# Top_DMX8x8A-v1.net
KiCad netlist of a schematic drawn in Altium Designer
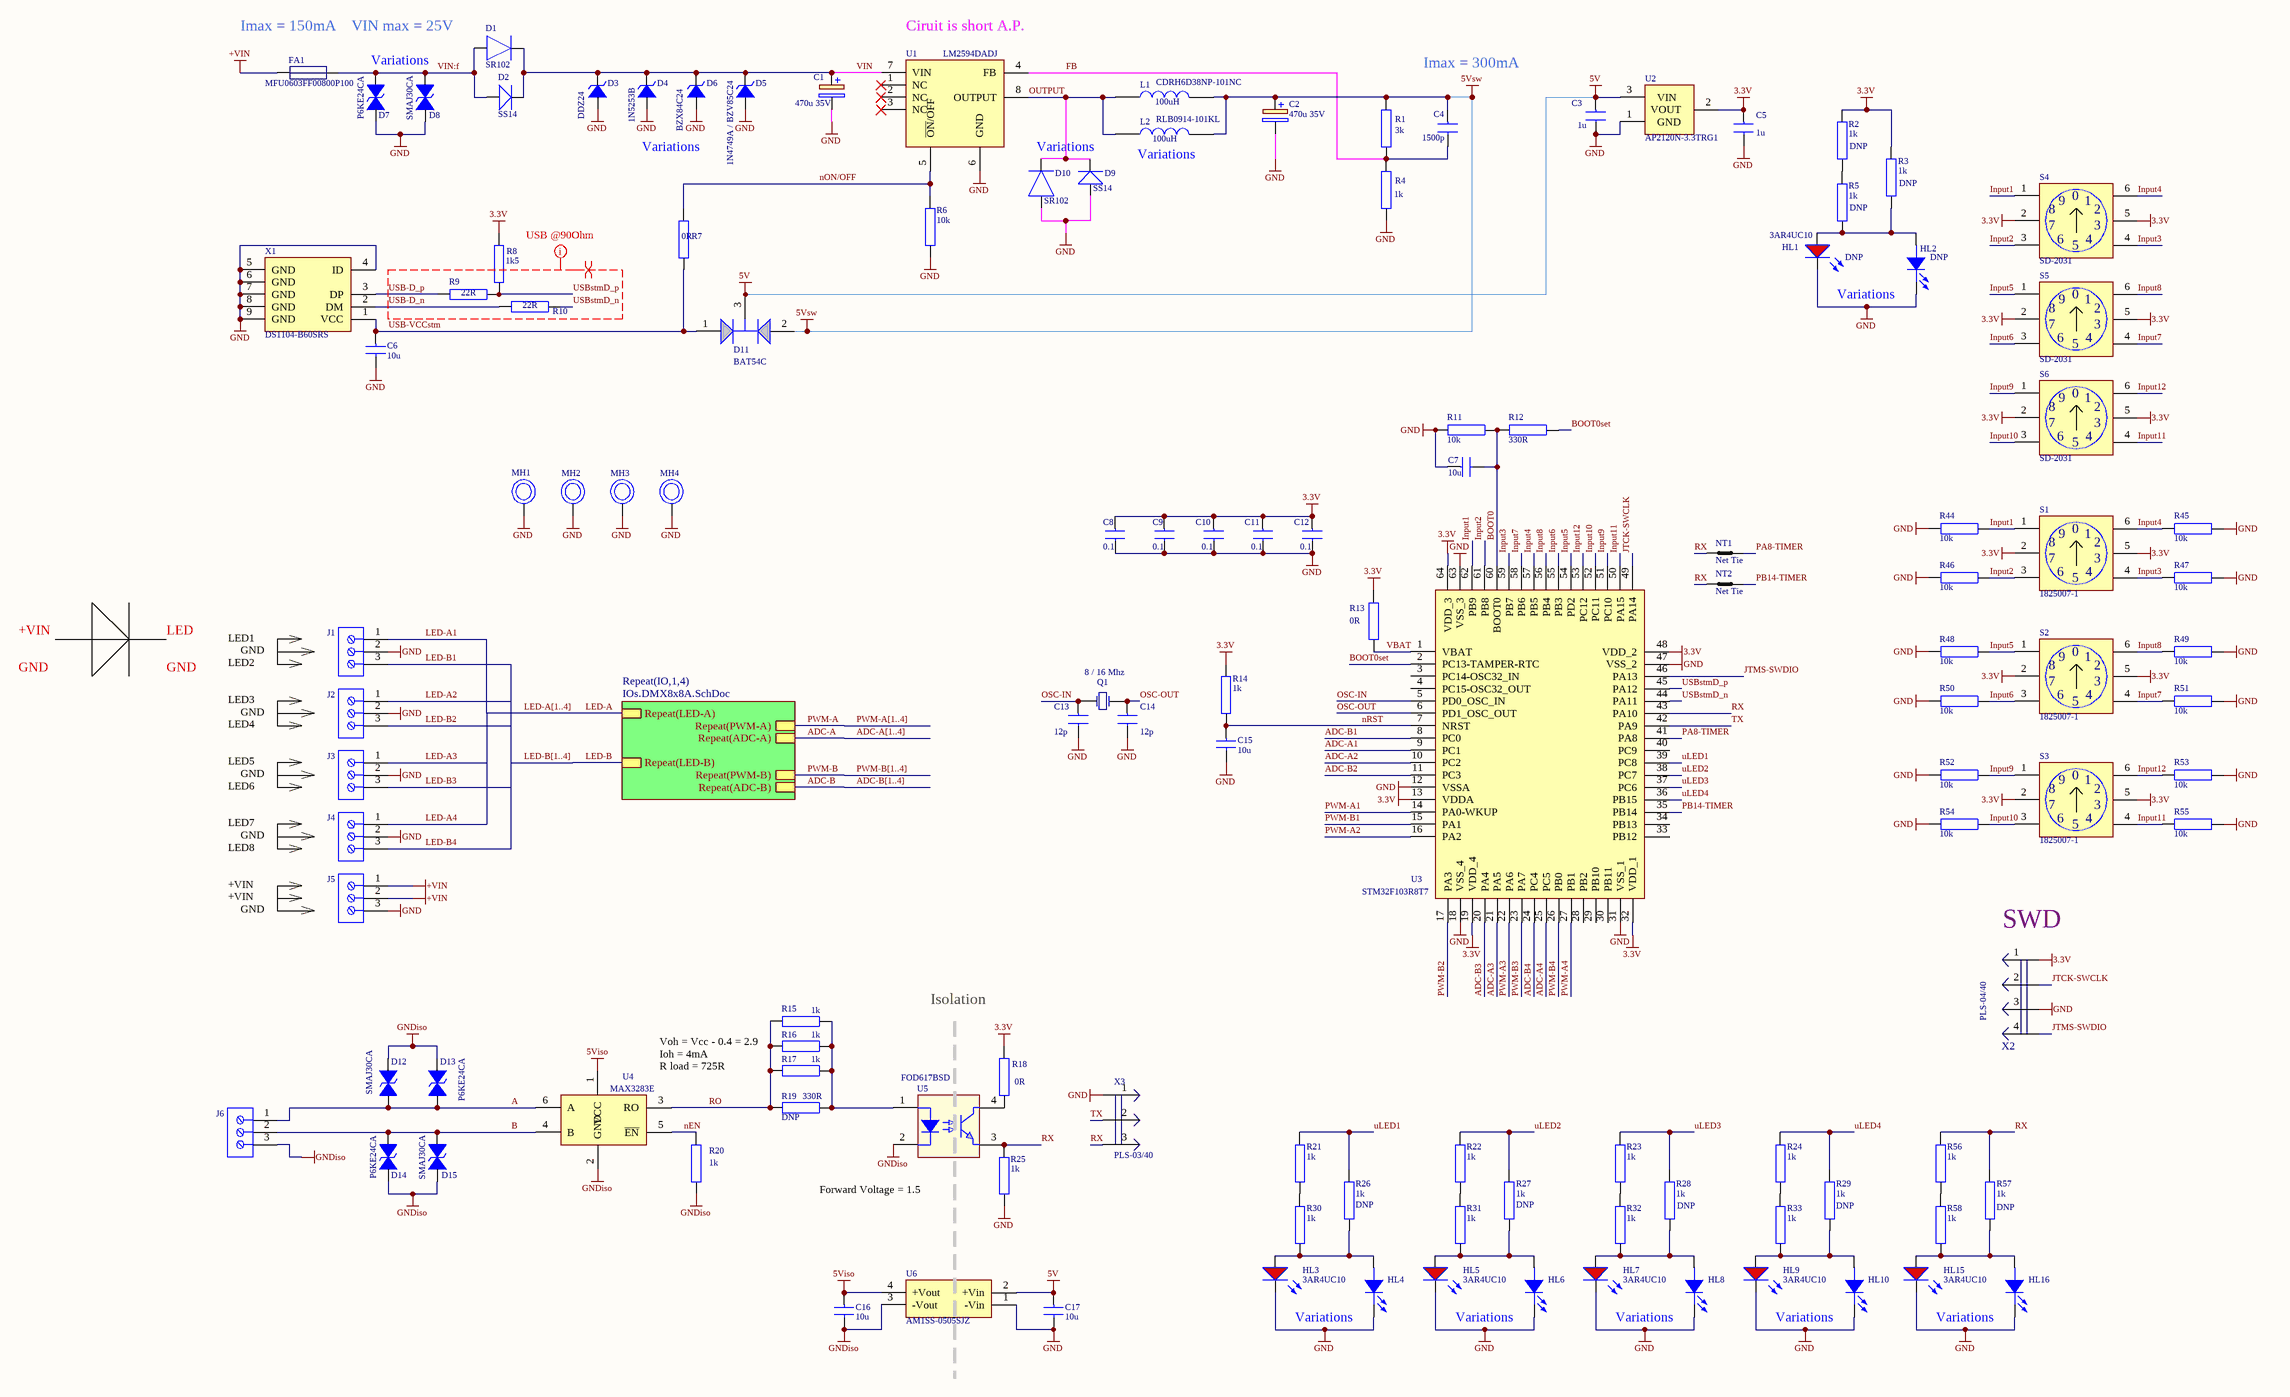
[diagram p0: Top.DMX8x8A-v1.SchDoc]

(export (version "E")
  (design (tool "Eeschema 10.0.6"))
  (components
    (comp (ref "C1")
      (value "470u 35V")
      (footprint "CAPPRD500W60D1025H1750")
      (description "Radial Lead Aluminum Electrolytic Capacitors")
      (fields (field (name "Comment") "35ZL470MEFC10X20"))
      (libsource (lib "DMX512") (part "35ZL470MEFC10X20"))
    )
    (comp (ref "C2")
      (value "470u 35V")
      (footprint "CAPPRD500W60D1025H1750")
      (description "Radial Lead Aluminum Electrolytic Capacitors")
      (fields (field (name "Comment") "35ZL470MEFC10X20"))
      (libsource (lib "DMX512") (part "35ZL470MEFC10X20"))
    )
    (comp (ref "C3")
      (value "1u")
      (footprint "Chip C 0402 - 1206")
      (description "Ceramic Chip Capacitor")
      (fields (field (name "Comment") "1u 50V 5%"))
      (libsource (lib "Capacitors") (part "Ceramic SMD Cap_R"))
    )
    (comp (ref "C4")
      (value "1500p")
      (footprint "Chip C 0402 - 1206")
      (description "Ceramic Chip Capacitor")
      (fields (field (name "Comment") "1500p 25V 20%"))
      (libsource (lib "Capacitors") (part "Ceramic SMD Cap_R"))
    )
    (comp (ref "C5")
      (value "1u")
      (footprint "Chip C 0402 - 1206")
      (description "Ceramic Chip Capacitor")
      (fields (field (name "Comment") "1u 50V 5%"))
      (libsource (lib "Capacitors") (part "Ceramic SMD Cap_R"))
    )
    (comp (ref "C6")
      (value "10u")
      (footprint "Chip C 0402 - 1206")
      (description "Ceramic Chip Capacitor")
      (fields (field (name "Comment") "10u 50V 5%"))
      (libsource (lib "Capacitors") (part "Ceramic SMD Cap_R"))
    )
    (comp (ref "C7")
      (value "10u")
      (footprint "Chip C 0402 - 1206")
      (description "Ceramic Chip Capacitor")
      (fields (field (name "Comment") "10u 50V 5%"))
      (libsource (lib "Capacitors") (part "Ceramic SMD Cap_R"))
    )
    (comp (ref "C8")
      (value "0.1")
      (footprint "Chip C 0402 - 1206")
      (description "Ceramic Chip Capacitor")
      (fields (field (name "Comment") "0.1 25V 20%"))
      (libsource (lib "Capacitors") (part "Ceramic SMD Cap_R"))
    )
    (comp (ref "C9")
      (value "0.1")
      (footprint "Chip C 0402 - 1206")
      (description "Ceramic Chip Capacitor")
      (fields (field (name "Comment") "0.1 25V 20%"))
      (libsource (lib "Capacitors") (part "Ceramic SMD Cap_R"))
    )
    (comp (ref "C10")
      (value "0.1")
      (footprint "Chip C 0402 - 1206")
      (description "Ceramic Chip Capacitor")
      (fields (field (name "Comment") "0.1 25V 20%"))
      (libsource (lib "Capacitors") (part "Ceramic SMD Cap_R"))
    )
    (comp (ref "C11")
      (value "0.1")
      (footprint "Chip C 0402 - 1206")
      (description "Ceramic Chip Capacitor")
      (fields (field (name "Comment") "0.1 25V 20%"))
      (libsource (lib "Capacitors") (part "Ceramic SMD Cap_R"))
    )
    (comp (ref "C12")
      (value "0.1")
      (footprint "Chip C 0402 - 1206")
      (description "Ceramic Chip Capacitor")
      (fields (field (name "Comment") "0.1 25V 20%"))
      (libsource (lib "Capacitors") (part "Ceramic SMD Cap_R"))
    )
    (comp (ref "C13")
      (value "12p")
      (footprint "Chip C 0402 - 1206")
      (description "Ceramic Chip Capacitor")
      (fields (field (name "Comment") "12p 25V 20%"))
      (libsource (lib "Capacitors") (part "Ceramic SMD Cap_R"))
    )
    (comp (ref "C14")
      (value "12p")
      (footprint "Chip C 0402 - 1206")
      (description "Ceramic Chip Capacitor")
      (fields (field (name "Comment") "12p 25V 20%"))
      (libsource (lib "Capacitors") (part "Ceramic SMD Cap_R"))
    )
    (comp (ref "C15")
      (value "10u")
      (footprint "Chip C 0402 - 1206")
      (description "Ceramic Chip Capacitor")
      (fields (field (name "Comment") "10u 50V 5%"))
      (libsource (lib "Capacitors") (part "Ceramic SMD Cap_R"))
    )
    (comp (ref "C16")
      (value "10u")
      (footprint "Chip C 0402 - 1206")
      (description "Ceramic Chip Capacitor")
      (fields (field (name "Comment") "10u 50V 5%"))
      (libsource (lib "Capacitors") (part "Ceramic SMD Cap_R"))
    )
    (comp (ref "C17")
      (value "10u")
      (footprint "Chip C 0402 - 1206")
      (description "Ceramic Chip Capacitor")
      (fields (field (name "Comment") "10u 50V 5%"))
      (libsource (lib "Capacitors") (part "Ceramic SMD Cap_R"))
    )
    (comp (ref "D1")
      (value "SR102")
      (footprint "DO-204AL (DO-41)")
      (description "Schottky Barrier Rectifier")
      (libsource (lib "DMX512") (part "SR102"))
    )
    (comp (ref "D2")
      (value "SS14")
      (footprint "DO-214AC (SMA)")
      (description "Surface Mount Schottky Barrier Rectifier 1A")
      (libsource (lib "DMX512") (part "SS14"))
    )
    (comp (ref "D3")
      (value "DDZ24")
      (footprint "SOD323F")
      (description "Zener 0.5w SOD323F")
      (fields (field (name "MFR") "Diodes Incorporated"))
      (libsource (lib "Diodes") (part "DDZ"))
    )
    (comp (ref "D4")
      (value "1N5253B")
      (footprint "DO-204AH (DO-35).SLDPRT")
      (description "Zener DO-35")
      (fields (field (name "MFR") "ON Semi"))
      (libsource (lib "DMX512") (part "1N5253B"))
    )
    (comp (ref "D5")
      (value "1N4749A / BZV85C24")
      (footprint "DO-204AL (DO-41)")
      (description "Zener DO-41")
      (libsource (lib "DMX512") (part "Zener DO-41"))
    )
    (comp (ref "D6")
      (value "BZX84C24")
      (footprint "SOT-23-3 (3)")
      (description "Zener regulator, 27V")
      (fields (field (name "MFR") "ON Semi"))
      (libsource (lib "Diodes") (part "BZX84C13LT1G"))
    )
    (comp (ref "D7")
      (value "P6KE24CA")
      (footprint "DIOAD1910W90L670D310 (DO-15)")
      (description "TVS Axial 600W Unipolar 24V")
      (libsource (lib "DMX512") (part "P6KE"))
    )
    (comp (ref "D8")
      (value "SMAJ30CA")
      (footprint "DO-214AC (SMA) biplar")
      (description "TVS Uni 30V")
      (fields (field (name "MFR") "ST"))
      (libsource (lib "TVS") (part "SMAJ30CA"))
    )
    (comp (ref "D9")
      (value "SS14")
      (footprint "DO-214AC (SMA)")
      (description "Surface Mount Schottky Barrier Rectifier 1A")
      (libsource (lib "DMX512") (part "SS12"))
    )
    (comp (ref "D10")
      (value "SR102")
      (footprint "DO-204AL (DO-41)")
      (description "Schottky Barrier Rectifier")
      (libsource (lib "DMX512") (part "SR102"))
    )
    (comp (ref "D11")
      (value "BAT54C")
      (footprint "SOT-23-3 (3)")
      (description "SURFACE MOUNT SCHOTTKY BARRIER DIODE")
      (libsource (lib "Diodes") (part "BAT54C"))
    )
    (comp (ref "D12")
      (value "SMAJ30CA")
      (footprint "DO-214AC (SMA) biplar")
      (description "TVS Uni 30V")
      (fields (field (name "MFR") "ST"))
      (libsource (lib "TVS") (part "SMAJ30CA"))
    )
    (comp (ref "D13")
      (value "P6KE24CA")
      (footprint "DIOAD1910W90L670D310 (DO-15)")
      (description "TVS Axial 600W Unipolar 24V")
      (libsource (lib "DMX512") (part "P6KE"))
    )
    (comp (ref "D14")
      (value "P6KE24CA")
      (footprint "DIOAD1910W90L670D310 (DO-15)")
      (description "TVS Axial 600W Unipolar 24V")
      (libsource (lib "DMX512") (part "P6KE"))
    )
    (comp (ref "D15")
      (value "SMAJ30CA")
      (footprint "DO-214AC (SMA) biplar")
      (description "TVS Uni 30V")
      (fields (field (name "MFR") "ST"))
      (libsource (lib "TVS") (part "SMAJ30CA"))
    )
    (comp (ref "FA1")
      (value "MFU0603FF00800P100")
      (footprint "FUSC1608X55N")
      (description "Thin Film Chip Fuse")
      (libsource (lib "DMX512") (part "Fuse MFU"))
    )
    (comp (ref "HL1")
      (value "3AR4UC10")
      (footprint "LED-2pin 2.54mm")
      (description "LED 3mm Red")
      (fields (field (name "DNP") "DNP"))
      (libsource (lib "DMX512") (part "3AR4UC10"))
    )
    (comp (ref "HL2")
      (value "? Any")
      (footprint "LED SMD 0805")
      (description "LED 0805")
      (fields (field (name "DNP") "DNP"))
      (libsource (lib "DMX512") (part "LED 0805"))
    )
    (comp (ref "HL3")
      (value "3AR4UC10")
      (footprint "LED-2pin 2.54mm")
      (description "LED 3mm Red")
      (libsource (lib "DMX512") (part "3AR4UC10"))
    )
    (comp (ref "HL4")
      (value "? Any")
      (footprint "LED SMD 0805")
      (description "LED 0805")
      (libsource (lib "DMX512") (part "LED 0805"))
    )
    (comp (ref "HL5")
      (value "3AR4UC10")
      (footprint "LED-2pin 2.54mm")
      (description "LED 3mm Red")
      (libsource (lib "DMX512") (part "3AR4UC10"))
    )
    (comp (ref "HL6")
      (value "? Any")
      (footprint "LED SMD 0805")
      (description "LED 0805")
      (libsource (lib "DMX512") (part "LED 0805"))
    )
    (comp (ref "HL7")
      (value "3AR4UC10")
      (footprint "LED-2pin 2.54mm")
      (description "LED 3mm Red")
      (libsource (lib "DMX512") (part "3AR4UC10"))
    )
    (comp (ref "HL8")
      (value "? Any")
      (footprint "LED SMD 0805")
      (description "LED 0805")
      (libsource (lib "DMX512") (part "LED 0805"))
    )
    (comp (ref "HL9")
      (value "3AR4UC10")
      (footprint "LED-2pin 2.54mm")
      (description "LED 3mm Red")
      (libsource (lib "DMX512") (part "3AR4UC10"))
    )
    (comp (ref "HL10")
      (value "? Any")
      (footprint "LED SMD 0805")
      (description "LED 0805")
      (libsource (lib "DMX512") (part "LED 0805"))
    )
    (comp (ref "HL15")
      (value "3AR4UC10")
      (footprint "LED-2pin 2.54mm")
      (description "LED 3mm Red")
      (libsource (lib "DMX512") (part "3AR4UC10"))
    )
    (comp (ref "HL16")
      (value "? Any")
      (footprint "LED SMD 0805")
      (description "LED 0805")
      (libsource (lib "DMX512") (part "LED 0805"))
    )
    (comp (ref "J1")
      (value "691134710003")
      (footprint "691134710003")
      (description "WR-TBL Serie 1347 Horizontal Cable Entry, Pressure Clamp, pitch 5mm, 3p")
      (fields (field (name "PUBLISHER") "Wurth Elektronik"))
      (libsource (lib "DMX512") (part "691134710003"))
    )
    (comp (ref "J2")
      (value "691134710003")
      (footprint "691134710003")
      (description "WR-TBL Serie 1347 Horizontal Cable Entry, Pressure Clamp, pitch 5mm, 3p")
      (fields (field (name "PUBLISHER") "Wurth Elektronik"))
      (libsource (lib "DMX512") (part "691134710003"))
    )
    (comp (ref "J3")
      (value "691134710003")
      (footprint "691134710003")
      (description "WR-TBL Serie 1347 Horizontal Cable Entry, Pressure Clamp, pitch 5mm, 3p")
      (fields (field (name "PUBLISHER") "Wurth Elektronik"))
      (libsource (lib "DMX512") (part "691134710003"))
    )
    (comp (ref "J4")
      (value "691134710003")
      (footprint "691134710003")
      (description "WR-TBL Serie 1347 Horizontal Cable Entry, Pressure Clamp, pitch 5mm, 3p")
      (fields (field (name "PUBLISHER") "Wurth Elektronik"))
      (libsource (lib "DMX512") (part "691134710003"))
    )
    (comp (ref "J5")
      (value "691134710003")
      (footprint "691134710003")
      (description "WR-TBL Serie 1347 Horizontal Cable Entry, Pressure Clamp, pitch 5mm, 3p")
      (fields (field (name "PUBLISHER") "Wurth Elektronik"))
      (libsource (lib "DMX512") (part "691134710003"))
    )
    (comp (ref "J6")
      (value "691134710003")
      (footprint "691134710003")
      (description "WR-TBL Serie 1347 Horizontal Cable Entry, Pressure Clamp, pitch 5mm, 3p")
      (fields (field (name "PUBLISHER") "Wurth Elektronik"))
      (libsource (lib "DMX512") (part "691134710003"))
    )
    (comp (ref "L1")
      (value "CDRH6D38NP-101NC")
      (footprint "INDPM6767X400N")
      (description "SMD Power Inductor 100uH 0.65A 265mOhms")
      (fields (field (name "MFR") "Sumida") (field (name "ALTIUM_VALUE") "100uH"))
      (libsource (lib "DMX512") (part "CDRH6D38NP"))
    )
    (comp (ref "L2")
      (value "RLB0914-101KL")
      (footprint "SamacSys:RLB0914")
      (description "Radial Fixed Through Hole Inductor 100uH Bourns 100 uH +/-10%")
      (fields (field (name "ALTIUM_VALUE") "100uH"))
      (libsource (lib "DMX512") (part "RLB0914-101KL"))
    )
    (comp (ref "MH1")
      (value "PMH")
      (footprint "Hole Pad 3.2x4mm")
      (description "Plated Mounting Hole")
      (libsource (lib "Misc") (part "PMH"))
    )
    (comp (ref "MH2")
      (value "PMH")
      (footprint "Hole Pad 3.2x4mm")
      (description "Plated Mounting Hole")
      (libsource (lib "Misc") (part "PMH"))
    )
    (comp (ref "MH3")
      (value "PMH")
      (footprint "Hole Pad 3.2x4mm")
      (description "Plated Mounting Hole")
      (libsource (lib "Misc") (part "PMH"))
    )
    (comp (ref "MH4")
      (value "PMH")
      (footprint "Hole Pad 3.2x4mm")
      (description "Plated Mounting Hole")
      (libsource (lib "Misc") (part "PMH"))
    )
    (comp (ref "NT1") (value "Net Tie") (footprint "Net Tie 0.3") (libsource (lib "Misc") (part "Net Tie")))
    (comp (ref "NT2") (value "Net Tie") (footprint "Net Tie 0.3") (libsource (lib "Misc") (part "Net Tie")))
    (comp (ref "Q1")
      (value "8 / 16 Mhz")
      (footprint "HC49SMD")
      (description "HC/49US (AT49) LOW PROFILE SURFACE\r\nMOUNT MICROPROCESSOR CRYSTAL")
      (fields (field (name "Comment") "Crystal HC/49US SMD"))
      (libsource (lib "DMX512") (part "Crystal HC49SMD"))
    )
    (comp (ref "R1")
      (value "3k")
      (footprint "Chip R 0402 - 1206")
      (description "Chip Resistor")
      (fields (field (name "Comment") "3k 5%"))
      (libsource (lib "Resistors") (part "Chip R"))
    )
    (comp (ref "R2")
      (value "1k")
      (footprint "Chip R 0402 - 1206")
      (description "Chip Resistor")
      (fields (field (name "DNP") "DNP") (field (name "Comment") "1k 5%"))
      (libsource (lib "Resistors") (part "Chip R"))
    )
    (comp (ref "R3")
      (value "1k")
      (footprint "Chip R 0402 - 1206")
      (description "Chip Resistor")
      (fields (field (name "DNP") "DNP") (field (name "Comment") "1k 5%"))
      (libsource (lib "Resistors") (part "Chip R"))
    )
    (comp (ref "R4")
      (value "1k")
      (footprint "Chip R 0402 - 1206")
      (description "Chip Resistor")
      (fields (field (name "Comment") "1k 5%"))
      (libsource (lib "Resistors") (part "Chip R"))
    )
    (comp (ref "R5")
      (value "1k")
      (footprint "Chip R 0402 - 1206")
      (description "Chip Resistor")
      (fields (field (name "DNP") "DNP") (field (name "Comment") "1k 5%"))
      (libsource (lib "Resistors") (part "Chip R"))
    )
    (comp (ref "R6")
      (value "10k")
      (footprint "Chip R 0402 - 1206")
      (description "Chip Resistor")
      (fields (field (name "Comment") "10k 5%"))
      (libsource (lib "Resistors") (part "Chip R"))
    )
    (comp (ref "R7")
      (value "0R")
      (footprint "Chip R 0402 - 1206")
      (description "Chip Resistor")
      (fields (field (name "Comment") "0R "))
      (libsource (lib "Resistors") (part "Chip R"))
    )
    (comp (ref "R8")
      (value "1k5")
      (footprint "Chip R 0402 - 1206")
      (description "Chip Resistor")
      (fields (field (name "Comment") "1k5 5%"))
      (libsource (lib "Resistors") (part "Chip R"))
    )
    (comp (ref "R9")
      (value "22R")
      (footprint "Chip R 0402 - 1206")
      (description "Chip Resistor")
      (fields (field (name "Comment") "22R 5%"))
      (libsource (lib "Resistors") (part "Chip R"))
    )
    (comp (ref "R10")
      (value "22R")
      (footprint "Chip R 0402 - 1206")
      (description "Chip Resistor")
      (fields (field (name "Comment") "22R 5%"))
      (libsource (lib "Resistors") (part "Chip R"))
    )
    (comp (ref "R11")
      (value "10k")
      (footprint "Chip R 0402 - 1206")
      (description "Chip Resistor")
      (fields (field (name "Comment") "10k 5%"))
      (libsource (lib "Resistors") (part "Chip R"))
    )
    (comp (ref "R12")
      (value "330R")
      (footprint "Chip R 0402 - 1206")
      (description "Chip Resistor")
      (fields (field (name "Comment") "330R 5%"))
      (libsource (lib "Resistors") (part "Chip R"))
    )
    (comp (ref "R13")
      (value "0R")
      (footprint "Chip R 0402 - 1206")
      (description "Chip Resistor")
      (fields (field (name "Comment") "0R "))
      (libsource (lib "DMX512") (part "Chip R"))
    )
    (comp (ref "R14")
      (value "1k")
      (footprint "Chip R 0402 - 1206")
      (description "Chip Resistor")
      (fields (field (name "Comment") "1k 5%"))
      (libsource (lib "Resistors") (part "Chip R"))
    )
    (comp (ref "R15")
      (value "1k")
      (footprint "Chip R 0402 - 1206")
      (description "Chip Resistor")
      (fields (field (name "Comment") "1k 5%"))
      (libsource (lib "Resistors") (part "Chip R"))
    )
    (comp (ref "R16")
      (value "1k")
      (footprint "Chip R 0402 - 1206")
      (description "Chip Resistor")
      (fields (field (name "Comment") "1k 5%"))
      (libsource (lib "Resistors") (part "Chip R"))
    )
    (comp (ref "R17")
      (value "1k")
      (footprint "Chip R 0402 - 1206")
      (description "Chip Resistor")
      (fields (field (name "Comment") "1k 5%"))
      (libsource (lib "Resistors") (part "Chip R"))
    )
    (comp (ref "R18")
      (value "0R")
      (footprint "Chip R 0402 - 1206")
      (description "Chip Resistor")
      (fields (field (name "Comment") "0R "))
      (libsource (lib "Resistors") (part "Chip R"))
    )
    (comp (ref "R19")
      (value "330R")
      (footprint "Chip R 0402 - 1206")
      (description "Chip Resistor")
      (fields (field (name "DNP") "DNP") (field (name "Comment") "330R 5%"))
      (libsource (lib "Resistors") (part "Chip R"))
    )
    (comp (ref "R20")
      (value "1k")
      (footprint "Chip R 0402 - 1206")
      (description "Chip Resistor")
      (fields (field (name "Comment") "1k 5%"))
      (libsource (lib "Resistors") (part "Chip R"))
    )
    (comp (ref "R21")
      (value "1k")
      (footprint "Chip R 0402 - 1206")
      (description "Chip Resistor")
      (fields (field (name "Comment") "1k 5%"))
      (libsource (lib "Resistors") (part "Chip R"))
    )
    (comp (ref "R22")
      (value "1k")
      (footprint "Chip R 0402 - 1206")
      (description "Chip Resistor")
      (fields (field (name "Comment") "1k 5%"))
      (libsource (lib "Resistors") (part "Chip R"))
    )
    (comp (ref "R23")
      (value "1k")
      (footprint "Chip R 0402 - 1206")
      (description "Chip Resistor")
      (fields (field (name "Comment") "1k 5%"))
      (libsource (lib "Resistors") (part "Chip R"))
    )
    (comp (ref "R24")
      (value "1k")
      (footprint "Chip R 0402 - 1206")
      (description "Chip Resistor")
      (fields (field (name "Comment") "1k 5%"))
      (libsource (lib "Resistors") (part "Chip R"))
    )
    (comp (ref "R25")
      (value "1k")
      (footprint "Chip R 0402 - 1206")
      (description "Chip Resistor")
      (fields (field (name "Comment") "1k 5%"))
      (libsource (lib "Resistors") (part "Chip R"))
    )
    (comp (ref "R26")
      (value "1k")
      (footprint "Chip R 0402 - 1206")
      (description "Chip Resistor")
      (fields (field (name "DNP") "DNP") (field (name "Comment") "1k 5%"))
      (libsource (lib "Resistors") (part "Chip R"))
    )
    (comp (ref "R27")
      (value "1k")
      (footprint "Chip R 0402 - 1206")
      (description "Chip Resistor")
      (fields (field (name "DNP") "DNP") (field (name "Comment") "1k 5%"))
      (libsource (lib "Resistors") (part "Chip R"))
    )
    (comp (ref "R28")
      (value "1k")
      (footprint "Chip R 0402 - 1206")
      (description "Chip Resistor")
      (fields (field (name "DNP") "DNP") (field (name "Comment") "1k 5%"))
      (libsource (lib "Resistors") (part "Chip R"))
    )
    (comp (ref "R29")
      (value "1k")
      (footprint "Chip R 0402 - 1206")
      (description "Chip Resistor")
      (fields (field (name "DNP") "DNP") (field (name "Comment") "1k 5%"))
      (libsource (lib "Resistors") (part "Chip R"))
    )
    (comp (ref "R30")
      (value "1k")
      (footprint "Chip R 0402 - 1206")
      (description "Chip Resistor")
      (fields (field (name "Comment") "1k 5%"))
      (libsource (lib "Resistors") (part "Chip R"))
    )
    (comp (ref "R31")
      (value "1k")
      (footprint "Chip R 0402 - 1206")
      (description "Chip Resistor")
      (fields (field (name "Comment") "1k 5%"))
      (libsource (lib "Resistors") (part "Chip R"))
    )
    (comp (ref "R32")
      (value "1k")
      (footprint "Chip R 0402 - 1206")
      (description "Chip Resistor")
      (fields (field (name "Comment") "1k 5%"))
      (libsource (lib "Resistors") (part "Chip R"))
    )
    (comp (ref "R33")
      (value "1k")
      (footprint "Chip R 0402 - 1206")
      (description "Chip Resistor")
      (fields (field (name "Comment") "1k 5%"))
      (libsource (lib "Resistors") (part "Chip R"))
    )
    (comp (ref "R44")
      (value "10k")
      (footprint "Chip R 0402 - 1206")
      (description "Chip Resistor")
      (fields (field (name "Comment") "10k 5%"))
      (libsource (lib "Resistors") (part "Chip R"))
    )
    (comp (ref "R45")
      (value "10k")
      (footprint "Chip R 0402 - 1206")
      (description "Chip Resistor")
      (fields (field (name "Comment") "10k 5%"))
      (libsource (lib "Resistors") (part "Chip R"))
    )
    (comp (ref "R46")
      (value "10k")
      (footprint "Chip R 0402 - 1206")
      (description "Chip Resistor")
      (fields (field (name "Comment") "10k 5%"))
      (libsource (lib "Resistors") (part "Chip R"))
    )
    (comp (ref "R47")
      (value "10k")
      (footprint "Chip R 0402 - 1206")
      (description "Chip Resistor")
      (fields (field (name "Comment") "10k 5%"))
      (libsource (lib "Resistors") (part "Chip R"))
    )
    (comp (ref "R48")
      (value "10k")
      (footprint "Chip R 0402 - 1206")
      (description "Chip Resistor")
      (fields (field (name "Comment") "10k 5%"))
      (libsource (lib "Resistors") (part "Chip R"))
    )
    (comp (ref "R49")
      (value "10k")
      (footprint "Chip R 0402 - 1206")
      (description "Chip Resistor")
      (fields (field (name "Comment") "10k 5%"))
      (libsource (lib "Resistors") (part "Chip R"))
    )
    (comp (ref "R50")
      (value "10k")
      (footprint "Chip R 0402 - 1206")
      (description "Chip Resistor")
      (fields (field (name "Comment") "10k 5%"))
      (libsource (lib "Resistors") (part "Chip R"))
    )
    (comp (ref "R51")
      (value "10k")
      (footprint "Chip R 0402 - 1206")
      (description "Chip Resistor")
      (fields (field (name "Comment") "10k 5%"))
      (libsource (lib "Resistors") (part "Chip R"))
    )
    (comp (ref "R52")
      (value "10k")
      (footprint "Chip R 0402 - 1206")
      (description "Chip Resistor")
      (fields (field (name "Comment") "10k 5%"))
      (libsource (lib "Resistors") (part "Chip R"))
    )
    (comp (ref "R53")
      (value "10k")
      (footprint "Chip R 0402 - 1206")
      (description "Chip Resistor")
      (fields (field (name "Comment") "10k 5%"))
      (libsource (lib "Resistors") (part "Chip R"))
    )
    (comp (ref "R54")
      (value "10k")
      (footprint "Chip R 0402 - 1206")
      (description "Chip Resistor")
      (fields (field (name "Comment") "10k 5%"))
      (libsource (lib "Resistors") (part "Chip R"))
    )
    (comp (ref "R55")
      (value "10k")
      (footprint "Chip R 0402 - 1206")
      (description "Chip Resistor")
      (fields (field (name "Comment") "10k 5%"))
      (libsource (lib "Resistors") (part "Chip R"))
    )
    (comp (ref "R56")
      (value "1k")
      (footprint "Chip R 0402 - 1206")
      (description "Chip Resistor")
      (fields (field (name "Comment") "1k 5%"))
      (libsource (lib "Resistors") (part "Chip R"))
    )
    (comp (ref "R57")
      (value "1k")
      (footprint "Chip R 0402 - 1206")
      (description "Chip Resistor")
      (fields (field (name "DNP") "DNP") (field (name "Comment") "1k 5%"))
      (libsource (lib "Resistors") (part "Chip R"))
    )
    (comp (ref "R58")
      (value "1k")
      (footprint "Chip R 0402 - 1206")
      (description "Chip Resistor")
      (fields (field (name "Comment") "1k 5%"))
      (libsource (lib "Resistors") (part "Chip R"))
    )
    (comp (ref "S1")
      (value "1825007-1")
      (footprint "1825007-1")
      (libsource (lib "DMX512") (part "1825007-1"))
    )
    (comp (ref "S2")
      (value "1825007-1")
      (footprint "1825007-1")
      (libsource (lib "DMX512") (part "1825007-1"))
    )
    (comp (ref "S3")
      (value "1825007-1")
      (footprint "1825007-1")
      (libsource (lib "DMX512") (part "1825007-1"))
    )
    (comp (ref "S4")
      (value "SD-2031")
      (footprint "SD-2031")
      (description "ROTARY CODED SWITCHES")
      (libsource (lib "DMX512") (part "SD-2031"))
    )
    (comp (ref "S5")
      (value "SD-2031")
      (footprint "SD-2031")
      (description "ROTARY CODED SWITCHES")
      (libsource (lib "DMX512") (part "SD-2031"))
    )
    (comp (ref "S6")
      (value "SD-2031")
      (footprint "SD-2031")
      (description "ROTARY CODED SWITCHES")
      (libsource (lib "DMX512") (part "SD-2031"))
    )
    (comp (ref "U1")
      (value "LM2594DADJ")
      (footprint "SOIC-8")
      (description "0.5 A, Step-Down Switching Regulator")
      (fields (field (name "MFR") "ON Semiconductor"))
      (libsource (lib "DMX512") (part "LM2594DADJ"))
    )
    (comp (ref "U2")
      (value "AP2120N-3.3TRG1")
      (footprint "DMX512:SOT-23-3 (3)")
      (description "High Speed, Extremely Low Noise LDO Regulator")
      (fields
        (field (name "MOUSER PART NUMBER") "621-AP2120N-3.3TRG1")
        (field (name "RS PART NUMBER") "8287334P")
      )
      (libsource (lib "DMX512") (part "AP2120N-3.3TRG1"))
    )
    (comp (ref "U3")
      (value "STM32F103R8T7")
      (footprint "LQFP64 (QFP50P1200X1200X160-64N)")
      (fields (field (name "MFR") "STMicroelectronics"))
      (libsource (lib "DMX512") (part "STM32F103R8T7"))
    )
    (comp (ref "U4")
      (value "MAX3283E")
      (footprint "SOT23-6 (SOT95P280X145-6N)")
      (description "15kV ESD-Protected 52Mbps, 3V to 5.5V,\r\nSOT23 RS-485/RS-422 True Fail-Safe Receiver")
      (fields
        (field (name "MANUFACTURER_PART_NUMBER") "MAX3283EAUT+T")
        (field (name "MOUSER PART NUMBER") "700-MAX3283EAUTT")
      )
      (libsource (lib "DMX512") (part "MAX3283E"))
    )
    (comp (ref "U5")
      (value "FOD617BSD")
      (footprint "FOD617BSD")
      (description "4-Pin High Operating Temperature\r\nPhototransistor Optocouplers")
      (fields
        (field (name "MANUFACTURER_PART_NUMBER") "FOD814")
        (field (name "MOUSER PART NUMBER") "512-FOD814")
      )
      (libsource (lib "DMX512") (part "FOD617BSD"))
    )
    (comp (ref "U6")
      (value "AM1SS-0505SJZ")
      (footprint "SamacSys:AM1S")
      (description "Isolated DC-DC Converter 1 Watt")
      (fields (field (name "MANUFACTURER_PART_NUMBER") "AM1SS-1205S-NZ"))
      (libsource (lib "DMX512") (part "AM1SS-0505SJZ"))
    )
    (comp (ref "X1")
      (value "DS1104-B60SRS")
      (footprint "DS1104-B60SRS")
      (description "mini USB on PCB")
      (libsource (lib "USB") (part "miniUSB"))
    )
    (comp (ref "X2")
      (value "PLS-04/40")
      (footprint "PLS-04")
      (description "Pin header, Vertcial, Strips, Male, 2.54mm pitch")
      (fields
        (field (name "MFR") "Бурый медведь")
        (field (name "HELPURL") "Y:\\LIBRARY\\Altium Designer\\Datasheets\\Connectors\\00789-Штыревые разъемы Платан.pdf")
      )
      (libsource (lib "Conx") (part "PLS-04"))
    )
    (comp (ref "X3")
      (value "PLS-03/40")
      (footprint "PLS-03")
      (description "PCB 2.54 PLS 03 Header")
      (fields
        (field (name "MFR") "Бурый медведь")
        (field (name "HELPURL") "Y:\\LIBRARY\\Altium Designer\\Datasheets\\Connectors\\00789-Штыревые разъемы Платан.pdf")
      )
      (libsource (lib "Connectors") (part "PLS-03"))
    )
  )
  (nets
    (net (code "1") (name "+VIN") (class "Default")
      (node (ref "FA1") (pin "1") (pinfunction "1_1") (pintype "passive"))
      (node (ref "J5") (pin "1") (pinfunction "1_1") (pintype "passive"))
      (node (ref "J5") (pin "2") (pinfunction "2_2") (pintype "passive"))
    )
    (net (code "2") (name "/A") (class "Default")
      (node (ref "D12") (pin "2") (pinfunction "2_2") (pintype "passive"))
      (node (ref "D13") (pin "2") (pinfunction "2_2") (pintype "passive"))
      (node (ref "J6") (pin "1") (pinfunction "1_1") (pintype "passive"))
      (node (ref "U4") (pin "6") (pinfunction "A_6") (pintype "passive"))
    )
    (net (code "4") (name "/ADC-A1") (class "Default")
      (node (ref "U3") (pin "9") (pinfunction "PC1_9") (pintype "passive"))
    )
    (net (code "5") (name "/ADC-A2") (class "Default")
      (node (ref "U3") (pin "10") (pinfunction "PC2_10") (pintype "passive"))
    )
    (net (code "6") (name "/ADC-A3") (class "Default")
      (node (ref "U3") (pin "21") (pinfunction "PA5_21") (pintype "passive"))
    )
    (net (code "7") (name "/ADC-A4") (class "Default")
      (node (ref "U3") (pin "25") (pinfunction "PC5_25") (pintype "passive"))
    )
    (net (code "10") (name "/ADC-B1") (class "Default")
      (node (ref "U3") (pin "8") (pinfunction "PC0_8") (pintype "passive"))
    )
    (net (code "11") (name "/ADC-B2") (class "Default")
      (node (ref "U3") (pin "11") (pinfunction "PC3_11") (pintype "passive"))
    )
    (net (code "12") (name "/ADC-B3") (class "Default")
      (node (ref "U3") (pin "20") (pinfunction "PA4_20") (pintype "passive"))
    )
    (net (code "13") (name "/ADC-B4") (class "Default")
      (node (ref "U3") (pin "24") (pinfunction "PC4_24") (pintype "passive"))
    )
    (net (code "15") (name "/B") (class "Default")
      (node (ref "D14") (pin "2") (pinfunction "2_2") (pintype "passive"))
      (node (ref "D15") (pin "2") (pinfunction "2_2") (pintype "passive"))
      (node (ref "J6") (pin "2") (pinfunction "2_2") (pintype "passive"))
      (node (ref "U4") (pin "4") (pinfunction "B_4") (pintype "passive"))
    )
    (net (code "16") (name "/BOOT0") (class "Default")
      (node (ref "C7") (pin "1") (pinfunction "1_1") (pintype "passive"))
      (node (ref "R11") (pin "2") (pinfunction "2_2") (pintype "passive"))
      (node (ref "R12") (pin "1") (pinfunction "1_1") (pintype "passive"))
      (node (ref "U3") (pin "60") (pinfunction "BOOT0_60") (pintype "passive"))
    )
    (net (code "17") (name "/BOOT0set") (class "Default")
      (node (ref "R12") (pin "2") (pinfunction "2_2") (pintype "passive"))
      (node (ref "U3") (pin "2") (pinfunction "PC13-TAMPER-RTC_2") (pintype "passive"))
    )
    (net (code "18") (name "/FB") (class "Default")
      (node (ref "C4") (pin "1") (pinfunction "1_1") (pintype "passive"))
      (node (ref "R1") (pin "1") (pinfunction "1_1") (pintype "passive"))
      (node (ref "R4") (pin "2") (pinfunction "2_2") (pintype "passive"))
      (node (ref "U1") (pin "4") (pinfunction "FB_4") (pintype "passive"))
    )
    (net (code "19") (name "/Input1") (class "Default")
      (node (ref "R44") (pin "2") (pinfunction "2_2") (pintype "passive"))
      (node (ref "S1") (pin "1") (pinfunction "1_1") (pintype "passive"))
      (node (ref "S4") (pin "1") (pinfunction "1_1") (pintype "passive"))
      (node (ref "U3") (pin "62") (pinfunction "PB9_62") (pintype "passive"))
    )
    (net (code "20") (name "/Input2") (class "Default")
      (node (ref "R46") (pin "2") (pinfunction "2_2") (pintype "passive"))
      (node (ref "S1") (pin "3") (pinfunction "3_3") (pintype "passive"))
      (node (ref "S4") (pin "3") (pinfunction "3_3") (pintype "passive"))
      (node (ref "U3") (pin "61") (pinfunction "PB8_61") (pintype "passive"))
    )
    (net (code "21") (name "/Input3") (class "Default")
      (node (ref "R47") (pin "2") (pinfunction "2_2") (pintype "passive"))
      (node (ref "S1") (pin "4") (pinfunction "4_4") (pintype "passive"))
      (node (ref "S4") (pin "4") (pinfunction "4_4") (pintype "passive"))
      (node (ref "U3") (pin "59") (pinfunction "PB7_59") (pintype "passive"))
    )
    (net (code "22") (name "/Input4") (class "Default")
      (node (ref "R45") (pin "2") (pinfunction "2_2") (pintype "passive"))
      (node (ref "S1") (pin "6") (pinfunction "6_6") (pintype "passive"))
      (node (ref "S4") (pin "6") (pinfunction "6_6") (pintype "passive"))
      (node (ref "U3") (pin "57") (pinfunction "PB5_57") (pintype "passive"))
    )
    (net (code "23") (name "/Input5") (class "Default")
      (node (ref "R48") (pin "2") (pinfunction "2_2") (pintype "passive"))
      (node (ref "S2") (pin "1") (pinfunction "1_1") (pintype "passive"))
      (node (ref "S5") (pin "1") (pinfunction "1_1") (pintype "passive"))
      (node (ref "U3") (pin "54") (pinfunction "PD2_54") (pintype "passive"))
    )
    (net (code "24") (name "/Input6") (class "Default")
      (node (ref "R50") (pin "2") (pinfunction "2_2") (pintype "passive"))
      (node (ref "S2") (pin "3") (pinfunction "3_3") (pintype "passive"))
      (node (ref "S5") (pin "3") (pinfunction "3_3") (pintype "passive"))
      (node (ref "U3") (pin "55") (pinfunction "PB3_55") (pintype "passive"))
    )
    (net (code "25") (name "/Input7") (class "Default")
      (node (ref "R51") (pin "2") (pinfunction "2_2") (pintype "passive"))
      (node (ref "S2") (pin "4") (pinfunction "4_4") (pintype "passive"))
      (node (ref "S5") (pin "4") (pinfunction "4_4") (pintype "passive"))
      (node (ref "U3") (pin "58") (pinfunction "PB6_58") (pintype "passive"))
    )
    (net (code "26") (name "/Input8") (class "Default")
      (node (ref "R49") (pin "2") (pinfunction "2_2") (pintype "passive"))
      (node (ref "S2") (pin "6") (pinfunction "6_6") (pintype "passive"))
      (node (ref "S5") (pin "6") (pinfunction "6_6") (pintype "passive"))
      (node (ref "U3") (pin "56") (pinfunction "PB4_56") (pintype "passive"))
    )
    (net (code "27") (name "/Input9") (class "Default")
      (node (ref "R52") (pin "2") (pinfunction "2_2") (pintype "passive"))
      (node (ref "S3") (pin "1") (pinfunction "1_1") (pintype "passive"))
      (node (ref "S6") (pin "1") (pinfunction "1_1") (pintype "passive"))
      (node (ref "U3") (pin "51") (pinfunction "PC10_51") (pintype "passive"))
    )
    (net (code "28") (name "/Input10") (class "Default")
      (node (ref "R54") (pin "2") (pinfunction "2_2") (pintype "passive"))
      (node (ref "S3") (pin "3") (pinfunction "3_3") (pintype "passive"))
      (node (ref "S6") (pin "3") (pinfunction "3_3") (pintype "passive"))
      (node (ref "U3") (pin "52") (pinfunction "PC11_52") (pintype "passive"))
    )
    (net (code "29") (name "/Input11") (class "Default")
      (node (ref "R55") (pin "2") (pinfunction "2_2") (pintype "passive"))
      (node (ref "S3") (pin "4") (pinfunction "4_4") (pintype "passive"))
      (node (ref "S6") (pin "4") (pinfunction "4_4") (pintype "passive"))
      (node (ref "U3") (pin "50") (pinfunction "PA15_50") (pintype "passive"))
    )
    (net (code "30") (name "/Input12") (class "Default")
      (node (ref "R53") (pin "2") (pinfunction "2_2") (pintype "passive"))
      (node (ref "S3") (pin "6") (pinfunction "6_6") (pintype "passive"))
      (node (ref "S6") (pin "6") (pinfunction "6_6") (pintype "passive"))
      (node (ref "U3") (pin "53") (pinfunction "PC12_53") (pintype "passive"))
    )
    (net (code "31") (name "/JTCK-SWCLK") (class "Default")
      (node (ref "U3") (pin "49") (pinfunction "PA14_49") (pintype "passive"))
      (node (ref "X2") (pin "2") (pinfunction "2_2") (pintype "passive"))
    )
    (net (code "32") (name "/JTMS-SWDIO") (class "Default")
      (node (ref "U3") (pin "46") (pinfunction "PA13_46") (pintype "passive"))
      (node (ref "X2") (pin "4") (pinfunction "4_4") (pintype "passive"))
    )
    (net (code "34") (name "/LED-A1") (class "Default")
      (node (ref "J1") (pin "1") (pinfunction "1_1") (pintype "passive"))
    )
    (net (code "35") (name "/LED-A2") (class "Default")
      (node (ref "J2") (pin "1") (pinfunction "1_1") (pintype "passive"))
    )
    (net (code "36") (name "/LED-A3") (class "Default")
      (node (ref "J3") (pin "1") (pinfunction "1_1") (pintype "passive"))
    )
    (net (code "37") (name "/LED-A4") (class "Default")
      (node (ref "J4") (pin "1") (pinfunction "1_1") (pintype "passive"))
    )
    (net (code "40") (name "/LED-B1") (class "Default")
      (node (ref "J1") (pin "3") (pinfunction "3_3") (pintype "passive"))
    )
    (net (code "41") (name "/LED-B2") (class "Default")
      (node (ref "J2") (pin "3") (pinfunction "3_3") (pintype "passive"))
    )
    (net (code "42") (name "/LED-B3") (class "Default")
      (node (ref "J3") (pin "3") (pinfunction "3_3") (pintype "passive"))
    )
    (net (code "43") (name "/LED-B4") (class "Default")
      (node (ref "J4") (pin "3") (pinfunction "3_3") (pintype "passive"))
    )
    (net (code "45") (name "/OSC-IN") (class "Default")
      (node (ref "C13") (pin "2") (pinfunction "2_2") (pintype "passive"))
      (node (ref "Q1") (pin "1") (pinfunction "1_1") (pintype "passive"))
      (node (ref "U3") (pin "5") (pinfunction "PD0_OSC_IN_5") (pintype "passive"))
    )
    (net (code "46") (name "/OSC-OUT") (class "Default")
      (node (ref "C14") (pin "2") (pinfunction "2_2") (pintype "passive"))
      (node (ref "Q1") (pin "2") (pinfunction "2_2") (pintype "passive"))
      (node (ref "U3") (pin "6") (pinfunction "PD1_OSC_OUT_6") (pintype "passive"))
    )
    (net (code "47") (name "/OUTPUT") (class "Default")
      (node (ref "D10") (pin "2") (pinfunction "A_2") (pintype "passive"))
      (node (ref "D9") (pin "2") (pinfunction "2_2") (pintype "passive"))
      (node (ref "L1") (pin "1") (pinfunction "1_1") (pintype "passive"))
      (node (ref "L2") (pin "1") (pinfunction "1_1") (pintype "passive"))
      (node (ref "U1") (pin "8") (pinfunction "OUTPUT_8") (pintype "passive"))
    )
    (net (code "48") (name "/PA8-TIMER") (class "Default")
      (node (ref "NT1") (pin "2") (pinfunction "2_2") (pintype "passive"))
      (node (ref "U3") (pin "41") (pinfunction "PA8_41") (pintype "passive"))
    )
    (net (code "49") (name "/PB14-TIMER") (class "Default")
      (node (ref "NT2") (pin "2") (pinfunction "2_2") (pintype "passive"))
      (node (ref "U3") (pin "35") (pinfunction "PB14_35") (pintype "passive"))
    )
    (net (code "51") (name "/PWM-A1") (class "Default")
      (node (ref "U3") (pin "14") (pinfunction "PA0-WKUP_14") (pintype "passive"))
    )
    (net (code "52") (name "/PWM-A2") (class "Default")
      (node (ref "U3") (pin "16") (pinfunction "PA2_16") (pintype "passive"))
    )
    (net (code "53") (name "/PWM-A3") (class "Default")
      (node (ref "U3") (pin "22") (pinfunction "PA6_22") (pintype "passive"))
    )
    (net (code "54") (name "/PWM-A4") (class "Default")
      (node (ref "U3") (pin "27") (pinfunction "PB1_27") (pintype "passive"))
    )
    (net (code "57") (name "/PWM-B1") (class "Default")
      (node (ref "U3") (pin "15") (pinfunction "PA1_15") (pintype "passive"))
    )
    (net (code "58") (name "/PWM-B2") (class "Default")
      (node (ref "U3") (pin "17") (pinfunction "PA3_17") (pintype "passive"))
    )
    (net (code "59") (name "/PWM-B3") (class "Default")
      (node (ref "U3") (pin "23") (pinfunction "PA7_23") (pintype "passive"))
    )
    (net (code "60") (name "/PWM-B4") (class "Default")
      (node (ref "U3") (pin "26") (pinfunction "PB0_26") (pintype "passive"))
    )
    (net (code "62") (name "/RO") (class "Default")
      (node (ref "R15") (pin "1") (pinfunction "1_1") (pintype "passive"))
      (node (ref "R16") (pin "1") (pinfunction "1_1") (pintype "passive"))
      (node (ref "R17") (pin "1") (pinfunction "1_1") (pintype "passive"))
      (node (ref "R19") (pin "1") (pinfunction "1_1") (pintype "passive"))
      (node (ref "U4") (pin "3") (pinfunction "RO_3") (pintype "passive"))
    )
    (net (code "63") (name "/RX") (class "Default")
      (node (ref "NT1") (pin "1") (pinfunction "1_1") (pintype "passive"))
      (node (ref "NT2") (pin "1") (pinfunction "1_1") (pintype "passive"))
      (node (ref "R25") (pin "2") (pinfunction "2_2") (pintype "passive"))
      (node (ref "R56") (pin "2") (pinfunction "2_2") (pintype "passive"))
      (node (ref "R57") (pin "2") (pinfunction "2_2") (pintype "passive"))
      (node (ref "U3") (pin "43") (pinfunction "PA10_43") (pintype "passive"))
      (node (ref "U5") (pin "3") (pinfunction "E_3") (pintype "passive"))
      (node (ref "X3") (pin "3") (pinfunction "3_3") (pintype "passive"))
    )
    (net (code "64") (name "/TX") (class "Default")
      (node (ref "U3") (pin "42") (pinfunction "PA9_42") (pintype "passive"))
      (node (ref "X3") (pin "2") (pinfunction "2_2") (pintype "passive"))
    )
    (net (code "65") (name "/USB-D_n") (class "Default")
      (node (ref "R10") (pin "1") (pinfunction "1_1") (pintype "passive"))
      (node (ref "X1") (pin "2") (pinfunction "DM_2") (pintype "passive"))
    )
    (net (code "66") (name "/USB-D_p") (class "Default")
      (node (ref "R9") (pin "1") (pinfunction "1_1") (pintype "passive"))
      (node (ref "X1") (pin "3") (pinfunction "DP_3") (pintype "passive"))
    )
    (net (code "67") (name "/USB-VCCstm") (class "Default")
      (node (ref "C6") (pin "2") (pinfunction "2_2") (pintype "passive"))
      (node (ref "D11") (pin "1") (pinfunction "A_1") (pintype "passive"))
      (node (ref "R7") (pin "1") (pinfunction "1_1") (pintype "passive"))
      (node (ref "X1") (pin "1") (pinfunction "VCC_1") (pintype "passive"))
    )
    (net (code "68") (name "/USBstmD_n") (class "Default")
      (node (ref "R10") (pin "2") (pinfunction "2_2") (pintype "passive"))
      (node (ref "U3") (pin "44") (pinfunction "PA11_44") (pintype "passive"))
    )
    (net (code "69") (name "/USBstmD_p") (class "Default")
      (node (ref "R8") (pin "1") (pinfunction "1_1") (pintype "passive"))
      (node (ref "R9") (pin "2") (pinfunction "2_2") (pintype "passive"))
      (node (ref "U3") (pin "45") (pinfunction "PA12_45") (pintype "passive"))
    )
    (net (code "70") (name "/VBAT") (class "Default")
      (node (ref "R13") (pin "1") (pinfunction "1_1") (pintype "passive"))
      (node (ref "U3") (pin "1") (pinfunction "VBAT_1") (pintype "passive"))
    )
    (net (code "71") (name "/VIN") (class "Default")
      (node (ref "C1") (pin "1") (pinfunction "+_1") (pintype "passive"))
      (node (ref "D1") (pin "2") (pinfunction "A_2") (pintype "passive"))
      (node (ref "D2") (pin "2") (pinfunction "2_2") (pintype "passive"))
      (node (ref "D3") (pin "1") (pinfunction "C_1") (pintype "passive"))
      (node (ref "D4") (pin "1") (pinfunction "1_1") (pintype "passive"))
      (node (ref "D5") (pin "1") (pinfunction "1_1") (pintype "passive"))
      (node (ref "D6") (pin "3") (pinfunction "3_3") (pintype "passive"))
      (node (ref "U1") (pin "7") (pinfunction "VIN_7") (pintype "passive"))
    )
    (net (code "72") (name "/VIN:f") (class "Default")
      (node (ref "D1") (pin "1") (pinfunction "K_1") (pintype "passive"))
      (node (ref "D2") (pin "1") (pinfunction "1_1") (pintype "passive"))
      (node (ref "D7") (pin "2") (pinfunction "2_2") (pintype "passive"))
      (node (ref "D8") (pin "2") (pinfunction "2_2") (pintype "passive"))
      (node (ref "FA1") (pin "2") (pinfunction "2_2") (pintype "passive"))
    )
    (net (code "73") (name "/nEN") (class "Default")
      (node (ref "R20") (pin "2") (pinfunction "2_2") (pintype "passive"))
      (node (ref "U4") (pin "5") (pinfunction "~{EN}_5") (pintype "passive"))
    )
    (net (code "74") (name "/nON{slash}OFF") (class "Default")
      (node (ref "R6") (pin "2") (pinfunction "2_2") (pintype "passive"))
      (node (ref "R7") (pin "2") (pinfunction "2_2") (pintype "passive"))
      (node (ref "U1") (pin "5") (pinfunction "~{ON}/OFF_5") (pintype "passive"))
    )
    (net (code "75") (name "/nRST") (class "Default")
      (node (ref "C15") (pin "2") (pinfunction "2_2") (pintype "passive"))
      (node (ref "R14") (pin "1") (pinfunction "1_1") (pintype "passive"))
      (node (ref "U3") (pin "7") (pinfunction "NRST_7") (pintype "passive"))
    )
    (net (code "76") (name "/uLED1") (class "Default")
      (node (ref "R21") (pin "2") (pinfunction "2_2") (pintype "passive"))
      (node (ref "R26") (pin "2") (pinfunction "2_2") (pintype "passive"))
      (node (ref "U3") (pin "39") (pinfunction "PC8_39") (pintype "passive"))
    )
    (net (code "77") (name "/uLED2") (class "Default")
      (node (ref "R22") (pin "2") (pinfunction "2_2") (pintype "passive"))
      (node (ref "R27") (pin "2") (pinfunction "2_2") (pintype "passive"))
      (node (ref "U3") (pin "38") (pinfunction "PC7_38") (pintype "passive"))
    )
    (net (code "78") (name "/uLED3") (class "Default")
      (node (ref "R23") (pin "2") (pinfunction "2_2") (pintype "passive"))
      (node (ref "R28") (pin "2") (pinfunction "2_2") (pintype "passive"))
      (node (ref "U3") (pin "37") (pinfunction "PC6_37") (pintype "passive"))
    )
    (net (code "79") (name "/uLED4") (class "Default")
      (node (ref "R24") (pin "2") (pinfunction "2_2") (pintype "passive"))
      (node (ref "R29") (pin "2") (pinfunction "2_2") (pintype "passive"))
      (node (ref "U3") (pin "36") (pinfunction "PB15_36") (pintype "passive"))
    )
    (net (code "80") (name "3.3V") (class "Default")
      (node (ref "C10") (pin "2") (pinfunction "2_2") (pintype "passive"))
      (node (ref "C11") (pin "2") (pinfunction "2_2") (pintype "passive"))
      (node (ref "C12") (pin "2") (pinfunction "2_2") (pintype "passive"))
      (node (ref "C5") (pin "2") (pinfunction "2_2") (pintype "passive"))
      (node (ref "C8") (pin "2") (pinfunction "2_2") (pintype "passive"))
      (node (ref "C9") (pin "2") (pinfunction "2_2") (pintype "passive"))
      (node (ref "R13") (pin "2") (pinfunction "2_2") (pintype "passive"))
      (node (ref "R14") (pin "2") (pinfunction "2_2") (pintype "passive"))
      (node (ref "R18") (pin "2") (pinfunction "2_2") (pintype "passive"))
      (node (ref "R2") (pin "2") (pinfunction "2_2") (pintype "passive"))
      (node (ref "R3") (pin "2") (pinfunction "2_2") (pintype "passive"))
      (node (ref "R8") (pin "2") (pinfunction "2_2") (pintype "passive"))
      (node (ref "S1") (pin "2") (pinfunction "2_2") (pintype "passive"))
      (node (ref "S1") (pin "5") (pinfunction "5_5") (pintype "passive"))
      (node (ref "S2") (pin "2") (pinfunction "2_2") (pintype "passive"))
      (node (ref "S2") (pin "5") (pinfunction "5_5") (pintype "passive"))
      (node (ref "S3") (pin "2") (pinfunction "2_2") (pintype "passive"))
      (node (ref "S3") (pin "5") (pinfunction "5_5") (pintype "passive"))
      (node (ref "S4") (pin "2") (pinfunction "2_2") (pintype "passive"))
      (node (ref "S4") (pin "5") (pinfunction "5_5") (pintype "passive"))
      (node (ref "S5") (pin "2") (pinfunction "2_2") (pintype "passive"))
      (node (ref "S5") (pin "5") (pinfunction "5_5") (pintype "passive"))
      (node (ref "S6") (pin "2") (pinfunction "2_2") (pintype "passive"))
      (node (ref "S6") (pin "5") (pinfunction "5_5") (pintype "passive"))
      (node (ref "U2") (pin "2") (pinfunction "VOUT_2") (pintype "passive"))
      (node (ref "U3") (pin "13") (pinfunction "VDDA_13") (pintype "passive"))
      (node (ref "U3") (pin "19") (pinfunction "VDD_4_19") (pintype "power_in"))
      (node (ref "U3") (pin "32") (pinfunction "VDD_1_32") (pintype "power_in"))
      (node (ref "U3") (pin "48") (pinfunction "VDD_2_48") (pintype "power_in"))
      (node (ref "U3") (pin "64") (pinfunction "VDD_3_64") (pintype "power_in"))
      (node (ref "X2") (pin "1") (pinfunction "1_1") (pintype "passive"))
    )
    (net (code "81") (name "5V") (class "Default")
      (node (ref "C17") (pin "2") (pinfunction "2_2") (pintype "passive"))
      (node (ref "C3") (pin "2") (pinfunction "2_2") (pintype "passive"))
      (node (ref "D11") (pin "3") (pinfunction "C_3") (pintype "passive"))
      (node (ref "U2") (pin "3") (pinfunction "VIN_3") (pintype "passive"))
      (node (ref "U6") (pin "2") (pinfunction "+Vin_2") (pintype "passive"))
    )
    (net (code "82") (name "5Viso") (class "Default")
      (node (ref "C16") (pin "2") (pinfunction "2_2") (pintype "passive"))
      (node (ref "U4") (pin "1") (pinfunction "VCC_1") (pintype "power_in"))
      (node (ref "U6") (pin "4") (pinfunction "+Vout_4") (pintype "passive"))
    )
    (net (code "83") (name "5Vsw") (class "Default")
      (node (ref "C2") (pin "1") (pinfunction "+_1") (pintype "passive"))
      (node (ref "C4") (pin "2") (pinfunction "2_2") (pintype "passive"))
      (node (ref "D11") (pin "2") (pinfunction "K_2") (pintype "passive"))
      (node (ref "L1") (pin "2") (pinfunction "2_2") (pintype "passive"))
      (node (ref "L2") (pin "2") (pinfunction "2_2") (pintype "passive"))
      (node (ref "R1") (pin "2") (pinfunction "2_2") (pintype "passive"))
    )
    (net (code "84") (name "GND") (class "Default")
      (node (ref "C1") (pin "2") (pinfunction "-_2") (pintype "passive"))
      (node (ref "C10") (pin "1") (pinfunction "1_1") (pintype "passive"))
      (node (ref "C11") (pin "1") (pinfunction "1_1") (pintype "passive"))
      (node (ref "C12") (pin "1") (pinfunction "1_1") (pintype "passive"))
      (node (ref "C13") (pin "1") (pinfunction "1_1") (pintype "passive"))
      (node (ref "C14") (pin "1") (pinfunction "1_1") (pintype "passive"))
      (node (ref "C15") (pin "1") (pinfunction "1_1") (pintype "passive"))
      (node (ref "C17") (pin "1") (pinfunction "1_1") (pintype "passive"))
      (node (ref "C2") (pin "2") (pinfunction "-_2") (pintype "passive"))
      (node (ref "C3") (pin "1") (pinfunction "1_1") (pintype "passive"))
      (node (ref "C5") (pin "1") (pinfunction "1_1") (pintype "passive"))
      (node (ref "C6") (pin "1") (pinfunction "1_1") (pintype "passive"))
      (node (ref "C7") (pin "2") (pinfunction "2_2") (pintype "passive"))
      (node (ref "C8") (pin "1") (pinfunction "1_1") (pintype "passive"))
      (node (ref "C9") (pin "1") (pinfunction "1_1") (pintype "passive"))
      (node (ref "D10") (pin "1") (pinfunction "K_1") (pintype "passive"))
      (node (ref "D3") (pin "2") (pinfunction "A_2") (pintype "passive"))
      (node (ref "D4") (pin "2") (pinfunction "2_2") (pintype "passive"))
      (node (ref "D5") (pin "2") (pinfunction "2_2") (pintype "passive"))
      (node (ref "D6") (pin "1") (pinfunction "1_1") (pintype "passive"))
      (node (ref "D7") (pin "1") (pinfunction "1_1") (pintype "passive"))
      (node (ref "D8") (pin "1") (pinfunction "1_1") (pintype "passive"))
      (node (ref "D9") (pin "1") (pinfunction "1_1") (pintype "passive"))
      (node (ref "HL1") (pin "2") (pinfunction "2_2") (pintype "passive"))
      (node (ref "HL10") (pin "2") (pinfunction "K_2") (pintype "passive"))
      (node (ref "HL15") (pin "2") (pinfunction "2_2") (pintype "passive"))
      (node (ref "HL16") (pin "2") (pinfunction "K_2") (pintype "passive"))
      (node (ref "HL2") (pin "2") (pinfunction "K_2") (pintype "passive"))
      (node (ref "HL3") (pin "2") (pinfunction "2_2") (pintype "passive"))
      (node (ref "HL4") (pin "2") (pinfunction "K_2") (pintype "passive"))
      (node (ref "HL5") (pin "2") (pinfunction "2_2") (pintype "passive"))
      (node (ref "HL6") (pin "2") (pinfunction "K_2") (pintype "passive"))
      (node (ref "HL7") (pin "2") (pinfunction "2_2") (pintype "passive"))
      (node (ref "HL8") (pin "2") (pinfunction "K_2") (pintype "passive"))
      (node (ref "HL9") (pin "2") (pinfunction "2_2") (pintype "passive"))
      (node (ref "J1") (pin "2") (pinfunction "2_2") (pintype "passive"))
      (node (ref "J2") (pin "2") (pinfunction "2_2") (pintype "passive"))
      (node (ref "J3") (pin "2") (pinfunction "2_2") (pintype "passive"))
      (node (ref "J4") (pin "2") (pinfunction "2_2") (pintype "passive"))
      (node (ref "J5") (pin "3") (pinfunction "3_3") (pintype "passive"))
      (node (ref "MH1") (pin "1") (pinfunction "1_1") (pintype "passive"))
      (node (ref "MH2") (pin "1") (pinfunction "1_1") (pintype "passive"))
      (node (ref "MH3") (pin "1") (pinfunction "1_1") (pintype "passive"))
      (node (ref "MH4") (pin "1") (pinfunction "1_1") (pintype "passive"))
      (node (ref "R11") (pin "1") (pinfunction "1_1") (pintype "passive"))
      (node (ref "R25") (pin "1") (pinfunction "1_1") (pintype "passive"))
      (node (ref "R4") (pin "1") (pinfunction "1_1") (pintype "passive"))
      (node (ref "R44") (pin "1") (pinfunction "1_1") (pintype "passive"))
      (node (ref "R45") (pin "1") (pinfunction "1_1") (pintype "passive"))
      (node (ref "R46") (pin "1") (pinfunction "1_1") (pintype "passive"))
      (node (ref "R47") (pin "1") (pinfunction "1_1") (pintype "passive"))
      (node (ref "R48") (pin "1") (pinfunction "1_1") (pintype "passive"))
      (node (ref "R49") (pin "1") (pinfunction "1_1") (pintype "passive"))
      (node (ref "R50") (pin "1") (pinfunction "1_1") (pintype "passive"))
      (node (ref "R51") (pin "1") (pinfunction "1_1") (pintype "passive"))
      (node (ref "R52") (pin "1") (pinfunction "1_1") (pintype "passive"))
      (node (ref "R53") (pin "1") (pinfunction "1_1") (pintype "passive"))
      (node (ref "R54") (pin "1") (pinfunction "1_1") (pintype "passive"))
      (node (ref "R55") (pin "1") (pinfunction "1_1") (pintype "passive"))
      (node (ref "R6") (pin "1") (pinfunction "1_1") (pintype "passive"))
      (node (ref "U1") (pin "6") (pinfunction "GND_6") (pintype "power_in"))
      (node (ref "U2") (pin "1") (pinfunction "GND_1") (pintype "passive"))
      (node (ref "U3") (pin "12") (pinfunction "VSSA_12") (pintype "passive"))
      (node (ref "U3") (pin "18") (pinfunction "VSS_4_18") (pintype "power_in"))
      (node (ref "U3") (pin "31") (pinfunction "VSS_1_31") (pintype "power_in"))
      (node (ref "U3") (pin "47") (pinfunction "VSS_2_47") (pintype "power_in"))
      (node (ref "U3") (pin "63") (pinfunction "VSS_3_63") (pintype "power_in"))
      (node (ref "U6") (pin "1") (pinfunction "-Vin_1") (pintype "passive"))
      (node (ref "X1") (pin "4") (pinfunction "ID_4") (pintype "passive"))
      (node (ref "X1") (pin "5") (pinfunction "GND_5") (pintype "passive"))
      (node (ref "X1") (pin "6") (pinfunction "GND_6") (pintype "passive"))
      (node (ref "X1") (pin "7") (pinfunction "GND_7") (pintype "passive"))
      (node (ref "X1") (pin "8") (pinfunction "GND_8") (pintype "passive"))
      (node (ref "X1") (pin "9") (pinfunction "GND_9") (pintype "passive"))
      (node (ref "X2") (pin "3") (pinfunction "3_3") (pintype "passive"))
      (node (ref "X3") (pin "1") (pinfunction "1_1") (pintype "passive"))
    )
    (net (code "85") (name "GNDiso") (class "Default")
      (node (ref "C16") (pin "1") (pinfunction "1_1") (pintype "passive"))
      (node (ref "D12") (pin "1") (pinfunction "1_1") (pintype "passive"))
      (node (ref "D13") (pin "1") (pinfunction "1_1") (pintype "passive"))
      (node (ref "D14") (pin "1") (pinfunction "1_1") (pintype "passive"))
      (node (ref "D15") (pin "1") (pinfunction "1_1") (pintype "passive"))
      (node (ref "J6") (pin "3") (pinfunction "3_3") (pintype "passive"))
      (node (ref "R20") (pin "1") (pinfunction "1_1") (pintype "passive"))
      (node (ref "U4") (pin "2") (pinfunction "GND_2") (pintype "power_in"))
      (node (ref "U5") (pin "2") (pinfunction "C_2") (pintype "passive"))
      (node (ref "U6") (pin "3") (pinfunction "-Vout_3") (pintype "passive"))
    )
    (net (code "86") (name "Net-(HL2-A)") (class "Default")
      (node (ref "HL1") (pin "1") (pinfunction "1_1") (pintype "passive"))
      (node (ref "HL2") (pin "1") (pinfunction "A_1") (pintype "passive"))
      (node (ref "R3") (pin "1") (pinfunction "1_1") (pintype "passive"))
      (node (ref "R5") (pin "1") (pinfunction "1_1") (pintype "passive"))
    )
    (net (code "87") (name "Net-(HL4-A)") (class "Default")
      (node (ref "HL3") (pin "1") (pinfunction "1_1") (pintype "passive"))
      (node (ref "HL4") (pin "1") (pinfunction "A_1") (pintype "passive"))
      (node (ref "R26") (pin "1") (pinfunction "1_1") (pintype "passive"))
      (node (ref "R30") (pin "1") (pinfunction "1_1") (pintype "passive"))
    )
    (net (code "88") (name "Net-(HL6-A)") (class "Default")
      (node (ref "HL5") (pin "1") (pinfunction "1_1") (pintype "passive"))
      (node (ref "HL6") (pin "1") (pinfunction "A_1") (pintype "passive"))
      (node (ref "R27") (pin "1") (pinfunction "1_1") (pintype "passive"))
      (node (ref "R31") (pin "1") (pinfunction "1_1") (pintype "passive"))
    )
    (net (code "89") (name "Net-(HL8-A)") (class "Default")
      (node (ref "HL7") (pin "1") (pinfunction "1_1") (pintype "passive"))
      (node (ref "HL8") (pin "1") (pinfunction "A_1") (pintype "passive"))
      (node (ref "R28") (pin "1") (pinfunction "1_1") (pintype "passive"))
      (node (ref "R32") (pin "1") (pinfunction "1_1") (pintype "passive"))
    )
    (net (code "90") (name "Net-(HL10-A)") (class "Default")
      (node (ref "HL10") (pin "1") (pinfunction "A_1") (pintype "passive"))
      (node (ref "HL9") (pin "1") (pinfunction "1_1") (pintype "passive"))
      (node (ref "R29") (pin "1") (pinfunction "1_1") (pintype "passive"))
      (node (ref "R33") (pin "1") (pinfunction "1_1") (pintype "passive"))
    )
    (net (code "91") (name "Net-(HL16-A)") (class "Default")
      (node (ref "HL15") (pin "1") (pinfunction "1_1") (pintype "passive"))
      (node (ref "HL16") (pin "1") (pinfunction "A_1") (pintype "passive"))
      (node (ref "R57") (pin "1") (pinfunction "1_1") (pintype "passive"))
      (node (ref "R58") (pin "1") (pinfunction "1_1") (pintype "passive"))
    )
    (net (code "92") (name "Net-(R2-Pad1)") (class "Default")
      (node (ref "R2") (pin "1") (pinfunction "1_1") (pintype "passive"))
      (node (ref "R5") (pin "2") (pinfunction "2_2") (pintype "passive"))
    )
    (net (code "93") (name "Net-(R18-Pad1)") (class "Default")
      (node (ref "R18") (pin "1") (pinfunction "1_1") (pintype "passive"))
      (node (ref "U5") (pin "4") (pinfunction "C_4") (pintype "passive"))
    )
    (net (code "94") (name "Net-(R21-Pad1)") (class "Default")
      (node (ref "R21") (pin "1") (pinfunction "1_1") (pintype "passive"))
      (node (ref "R30") (pin "2") (pinfunction "2_2") (pintype "passive"))
    )
    (net (code "95") (name "Net-(R22-Pad1)") (class "Default")
      (node (ref "R22") (pin "1") (pinfunction "1_1") (pintype "passive"))
      (node (ref "R31") (pin "2") (pinfunction "2_2") (pintype "passive"))
    )
    (net (code "96") (name "Net-(R23-Pad1)") (class "Default")
      (node (ref "R23") (pin "1") (pinfunction "1_1") (pintype "passive"))
      (node (ref "R32") (pin "2") (pinfunction "2_2") (pintype "passive"))
    )
    (net (code "97") (name "Net-(R24-Pad1)") (class "Default")
      (node (ref "R24") (pin "1") (pinfunction "1_1") (pintype "passive"))
      (node (ref "R33") (pin "2") (pinfunction "2_2") (pintype "passive"))
    )
    (net (code "98") (name "Net-(R56-Pad1)") (class "Default")
      (node (ref "R56") (pin "1") (pinfunction "1_1") (pintype "passive"))
      (node (ref "R58") (pin "2") (pinfunction "2_2") (pintype "passive"))
    )
    (net (code "99") (name "Net-(U5-A)") (class "Default")
      (node (ref "R15") (pin "2") (pinfunction "2_2") (pintype "passive"))
      (node (ref "R16") (pin "2") (pinfunction "2_2") (pintype "passive"))
      (node (ref "R17") (pin "2") (pinfunction "2_2") (pintype "passive"))
      (node (ref "R19") (pin "2") (pinfunction "2_2") (pintype "passive"))
      (node (ref "U5") (pin "1") (pinfunction "A_1") (pintype "passive"))
    )
    (net (code "100") (name "unconnected-(U1-NC-Pad1)") (class "Default")
      (node (ref "U1") (pin "1") (pinfunction "NC_1") (pintype "passive+no_connect"))
    )
    (net (code "101") (name "unconnected-(U1-NC-Pad2)") (class "Default")
      (node (ref "U1") (pin "2") (pinfunction "NC_2") (pintype "passive+no_connect"))
    )
    (net (code "102") (name "unconnected-(U1-NC-Pad3)") (class "Default")
      (node (ref "U1") (pin "3") (pinfunction "NC_3") (pintype "passive+no_connect"))
    )
    (net (code "103") (name "unconnected-(U3-PB2-Pad28)") (class "Default")
      (node (ref "U3") (pin "28") (pinfunction "PB2_28") (pintype "passive"))
    )
    (net (code "104") (name "unconnected-(U3-PB10-Pad29)") (class "Default")
      (node (ref "U3") (pin "29") (pinfunction "PB10_29") (pintype "passive"))
    )
    (net (code "105") (name "unconnected-(U3-PB11-Pad30)") (class "Default")
      (node (ref "U3") (pin "30") (pinfunction "PB11_30") (pintype "passive"))
    )
    (net (code "106") (name "unconnected-(U3-PB12-Pad33)") (class "Default")
      (node (ref "U3") (pin "33") (pinfunction "PB12_33") (pintype "passive"))
    )
    (net (code "107") (name "unconnected-(U3-PB13-Pad34)") (class "Default")
      (node (ref "U3") (pin "34") (pinfunction "PB13_34") (pintype "passive"))
    )
    (net (code "108") (name "unconnected-(U3-PC9-Pad40)") (class "Default")
      (node (ref "U3") (pin "40") (pinfunction "PC9_40") (pintype "passive"))
    )
    (net (code "109") (name "unconnected-(U3-PC14-OSC32_IN-Pad3)") (class "Default")
      (node (ref "U3") (pin "3") (pinfunction "PC14-OSC32_IN_3") (pintype "passive"))
    )
    (net (code "110") (name "unconnected-(U3-PC15-OSC32_OUT-Pad4)") (class "Default")
      (node (ref "U3") (pin "4") (pinfunction "PC15-OSC32_OUT_4") (pintype "passive"))
    )
  )
)
